# backplane.net
KiCad netlist of a schematic drawn in EAGLE
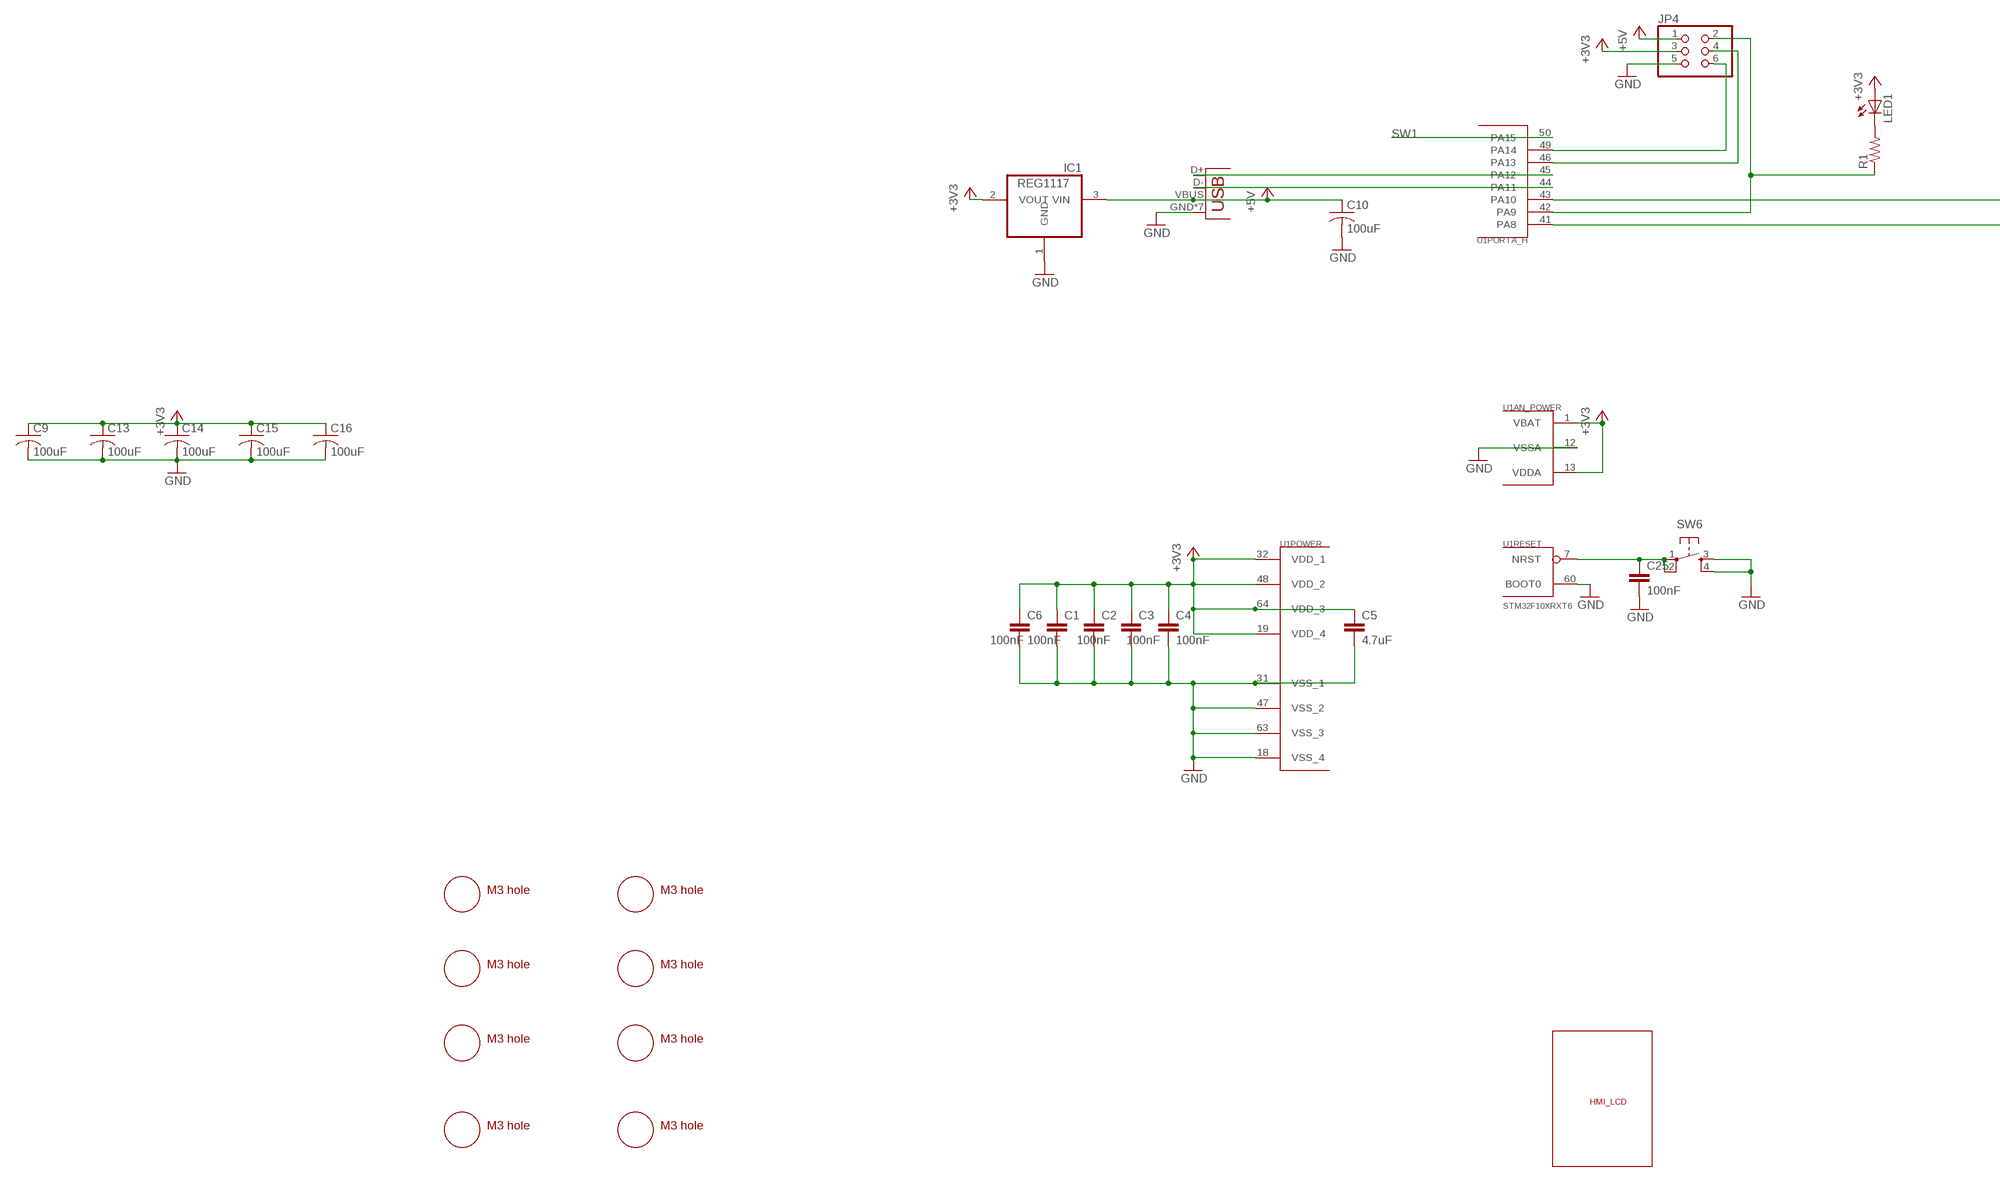
[diagram p0: schematic, sheet 1, part 1 of 2]
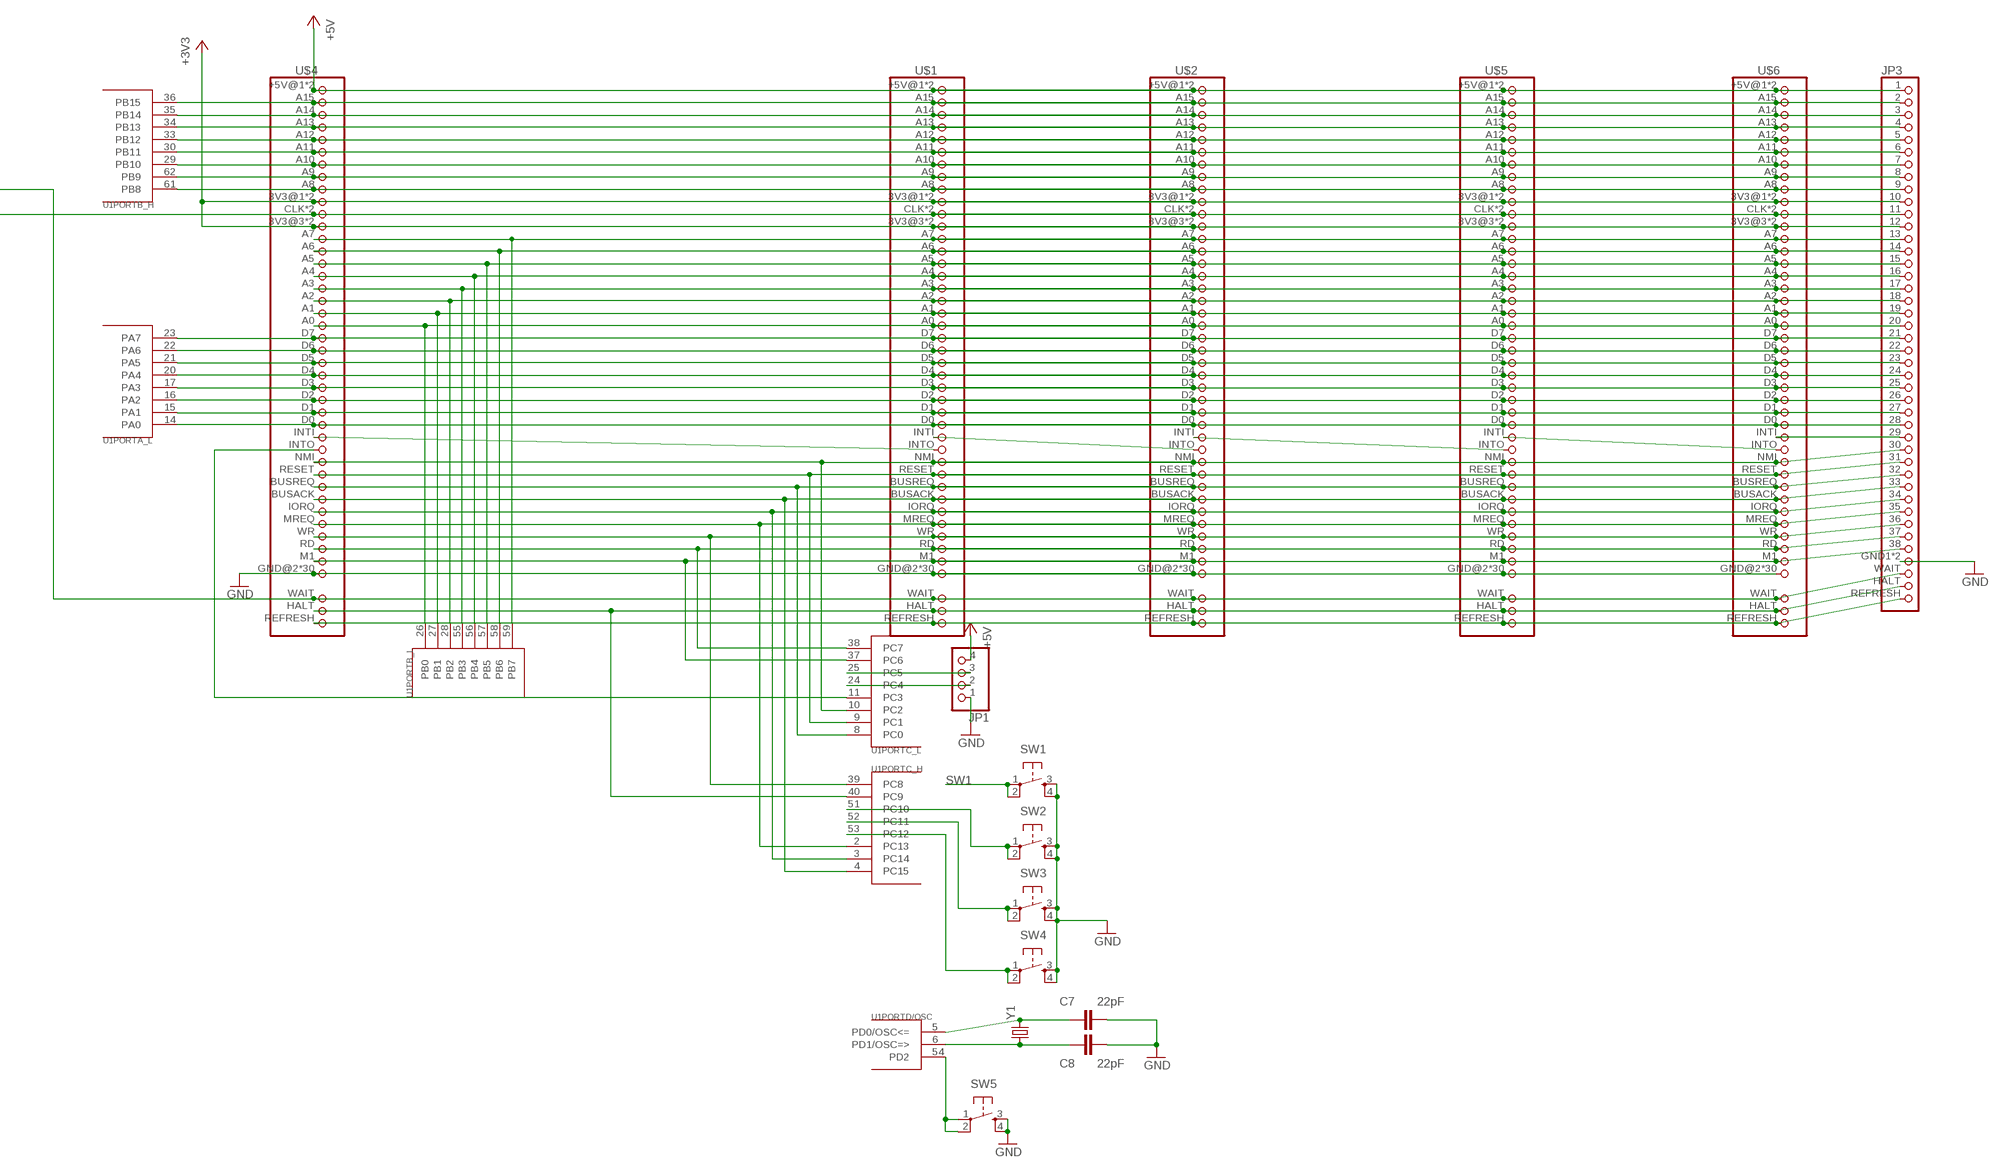
[diagram p1: schematic, sheet 1, part 2 of 2]

(export (version "E")
  (design (tool "Eeschema 10.0.6"))
  (components
    (comp (ref "C1")
      (value "100nF")
      (footprint "eagle-import:0805")
      (libsource (lib "eagle-import") (part "CAP0805"))
    )
    (comp (ref "C2")
      (value "100nF")
      (footprint "eagle-import:0805")
      (libsource (lib "eagle-import") (part "CAP0805"))
    )
    (comp (ref "C3")
      (value "100nF")
      (footprint "eagle-import:0805")
      (libsource (lib "eagle-import") (part "CAP0805"))
    )
    (comp (ref "C4")
      (value "100nF")
      (footprint "eagle-import:0805")
      (libsource (lib "eagle-import") (part "CAP0805"))
    )
    (comp (ref "C5")
      (value "4.7uF")
      (footprint "eagle-import:0805")
      (libsource (lib "eagle-import") (part "CAP0805"))
    )
    (comp (ref "C6")
      (value "100nF")
      (footprint "eagle-import:0805")
      (libsource (lib "eagle-import") (part "CAP0805"))
    )
    (comp (ref "C7")
      (value "22pF")
      (footprint "eagle-import:0805")
      (libsource (lib "eagle-import") (part "CAP0805"))
    )
    (comp (ref "C8")
      (value "22pF")
      (footprint "eagle-import:0805")
      (libsource (lib "eagle-import") (part "CAP0805"))
    )
    (comp (ref "C9")
      (value "100uF")
      (footprint "eagle-import:C1210")
      (libsource (lib "eagle-import") (part "C-USC1210"))
    )
    (comp (ref "C10")
      (value "100uF")
      (footprint "eagle-import:C1210")
      (libsource (lib "eagle-import") (part "C-USC1210"))
    )
    (comp (ref "C13")
      (value "100uF")
      (footprint "eagle-import:C1210")
      (libsource (lib "eagle-import") (part "C-USC1210"))
    )
    (comp (ref "C14")
      (value "100uF")
      (footprint "eagle-import:C1210")
      (libsource (lib "eagle-import") (part "C-USC1210"))
    )
    (comp (ref "C15")
      (value "100uF")
      (footprint "eagle-import:C1210")
      (libsource (lib "eagle-import") (part "C-USC1210"))
    )
    (comp (ref "C16")
      (value "100uF")
      (footprint "eagle-import:C1210")
      (libsource (lib "eagle-import") (part "C-USC1210"))
    )
    (comp (ref "C25")
      (value "100nF")
      (footprint "eagle-import:0805")
      (libsource (lib "eagle-import") (part "CAP0805"))
    )
    (comp (ref "IC1")
      (value "REG1117")
      (footprint "eagle-import:SOT223")
      (libsource (lib "eagle-import") (part "REG1117"))
    )
    (comp (ref "J1")
      (value "USB-MICROB")
      (footprint "eagle-import:USB-MICROB")
      (libsource (lib "eagle-import") (part "USB-MICROB"))
    )
    (comp (ref "JP1")
      (value "PINHD-1X4")
      (footprint "eagle-import:1X04")
      (libsource (lib "eagle-import") (part "PINHD-1X4"))
    )
    (comp (ref "JP3")
      (value "PINHD-1X38")
      (footprint "eagle-import:1X38")
      (libsource (lib "eagle-import") (part "PINHD-1X38"))
    )
    (comp (ref "JP4")
      (value "PINHD-2X3")
      (footprint "eagle-import:2X03")
      (libsource (lib "eagle-import") (part "PINHD-2X3"))
    )
    (comp (ref "LED1")
      (value "LEDCHIP-LED0805")
      (footprint "eagle-import:CHIP-LED0805")
      (libsource (lib "eagle-import") (part "LEDCHIP-LED0805"))
    )
    (comp (ref "R1")
      (value "R-US_R0805")
      (footprint "eagle-import:R0805")
      (libsource (lib "eagle-import") (part "R-US_R0805"))
    )
    (comp (ref "SW1")
      (value "SWITCH_SPST_4_PINSQUARE")
      (footprint "eagle-import:TACTILE-SWITCH-SMD")
      (libsource (lib "eagle-import") (part "SWITCH_SPST_4_PINSQUARE"))
    )
    (comp (ref "SW2")
      (value "SWITCH_SPST_4_PINSQUARE")
      (footprint "eagle-import:TACTILE-SWITCH-SMD")
      (libsource (lib "eagle-import") (part "SWITCH_SPST_4_PINSQUARE"))
    )
    (comp (ref "SW3")
      (value "SWITCH_SPST_4_PINSQUARE")
      (footprint "eagle-import:TACTILE-SWITCH-SMD")
      (libsource (lib "eagle-import") (part "SWITCH_SPST_4_PINSQUARE"))
    )
    (comp (ref "SW4")
      (value "SWITCH_SPST_4_PINSQUARE")
      (footprint "eagle-import:TACTILE-SWITCH-SMD")
      (libsource (lib "eagle-import") (part "SWITCH_SPST_4_PINSQUARE"))
    )
    (comp (ref "SW5")
      (value "SWITCH_SPST_4_PINSQUARE")
      (footprint "eagle-import:TACTILE-SWITCH-SMD")
      (libsource (lib "eagle-import") (part "SWITCH_SPST_4_PINSQUARE"))
    )
    (comp (ref "SW6")
      (value "SWITCH_SPST_4_PINSQUARE")
      (footprint "eagle-import:TACTILE-SWITCH-SMD")
      (libsource (lib "eagle-import") (part "SWITCH_SPST_4_PINSQUARE"))
    )
    (comp (ref "U$1")
      (value "FAP_BUS")
      (footprint "eagle-import:2X38")
      (libsource (lib "eagle-import") (part "FAP_BUS"))
    )
    (comp (ref "U$2")
      (value "FAP_BUS")
      (footprint "eagle-import:2X38")
      (libsource (lib "eagle-import") (part "FAP_BUS"))
    )
    (comp (ref "U$3")
      (value "HMI_LCD")
      (footprint "eagle-import:HMI_LCD")
      (libsource (lib "eagle-import") (part "HMI_LCD"))
    )
    (comp (ref "U$4")
      (value "FAP_BUS")
      (footprint "eagle-import:2X38")
      (libsource (lib "eagle-import") (part "FAP_BUS"))
    )
    (comp (ref "U$5")
      (value "FAP_BUS")
      (footprint "eagle-import:2X38")
      (libsource (lib "eagle-import") (part "FAP_BUS"))
    )
    (comp (ref "U$6")
      (value "FAP_BUS")
      (footprint "eagle-import:2X38")
      (libsource (lib "eagle-import") (part "FAP_BUS"))
    )
    (comp (ref "U$7")
      (value "M3_MOUNTING_HOLE")
      (footprint "eagle-import:M3_MOUNTING_HOLE_PACK")
      (libsource (lib "eagle-import") (part "M3_MOUNTING_HOLE"))
    )
    (comp (ref "U$8")
      (value "M3_MOUNTING_HOLE")
      (footprint "eagle-import:M3_MOUNTING_HOLE_PACK")
      (libsource (lib "eagle-import") (part "M3_MOUNTING_HOLE"))
    )
    (comp (ref "U$9")
      (value "M3_MOUNTING_HOLE")
      (footprint "eagle-import:M3_MOUNTING_HOLE_PACK")
      (libsource (lib "eagle-import") (part "M3_MOUNTING_HOLE"))
    )
    (comp (ref "U$10")
      (value "M3_MOUNTING_HOLE")
      (footprint "eagle-import:M3_MOUNTING_HOLE_PACK")
      (libsource (lib "eagle-import") (part "M3_MOUNTING_HOLE"))
    )
    (comp (ref "U$11")
      (value "M3_MOUNTING_HOLE")
      (footprint "eagle-import:M3_MOUNTING_HOLE_PACK")
      (libsource (lib "eagle-import") (part "M3_MOUNTING_HOLE"))
    )
    (comp (ref "U$12")
      (value "M3_MOUNTING_HOLE")
      (footprint "eagle-import:M3_MOUNTING_HOLE_PACK")
      (libsource (lib "eagle-import") (part "M3_MOUNTING_HOLE"))
    )
    (comp (ref "U$13")
      (value "M3_MOUNTING_HOLE")
      (footprint "eagle-import:M3_MOUNTING_HOLE_PACK")
      (libsource (lib "eagle-import") (part "M3_MOUNTING_HOLE"))
    )
    (comp (ref "U$14")
      (value "M3_MOUNTING_HOLE")
      (footprint "eagle-import:M3_MOUNTING_HOLE_PACK")
      (libsource (lib "eagle-import") (part "M3_MOUNTING_HOLE"))
    )
    (comp (ref "U1")
      (value "STM32F10XRXT6")
      (footprint "eagle-import:TQFP64")
      (libsource (lib "eagle-import") (part "STM32F10XRXT6"))
    )
    (comp (ref "Y1")
      (value "CRYSTALHC49US")
      (footprint "eagle-import:HC49US")
      (libsource (lib "eagle-import") (part "CRYSTALHC49US"))
    )
  )
  (nets
    (net (code "1") (name "+3V3") (class "Default")
      (node (ref "C1") (pin "1") (pinfunction "1_1") (pintype "passive"))
      (node (ref "C13") (pin "1") (pinfunction "1_1") (pintype "passive"))
      (node (ref "C14") (pin "1") (pinfunction "1_1") (pintype "passive"))
      (node (ref "C15") (pin "1") (pinfunction "1_1") (pintype "passive"))
      (node (ref "C16") (pin "1") (pinfunction "1_1") (pintype "passive"))
      (node (ref "C2") (pin "1") (pinfunction "1_1") (pintype "passive"))
      (node (ref "C3") (pin "1") (pinfunction "1_1") (pintype "passive"))
      (node (ref "C4") (pin "1") (pinfunction "1_1") (pintype "passive"))
      (node (ref "C5") (pin "1") (pinfunction "1_1") (pintype "passive"))
      (node (ref "C6") (pin "1") (pinfunction "1_1") (pintype "passive"))
      (node (ref "C9") (pin "1") (pinfunction "1_1") (pintype "passive"))
      (node (ref "IC1") (pin "2") (pinfunction "VOUT_2") (pintype "output"))
      (node (ref "JP3") (pin "10") (pinfunction "10_10") (pintype "passive"))
      (node (ref "JP3") (pin "12") (pinfunction "12_12") (pintype "passive"))
      (node (ref "JP4") (pin "3") (pinfunction "3_3") (pintype "passive"))
      (node (ref "LED1") (pin "A") (pinfunction "A_A") (pintype "passive"))
      (node (ref "U$1") (pin "3V3@1") (pinfunction "10_3V3@1") (pintype "passive"))
      (node (ref "U$1") (pin "3V3@2") (pinfunction "10_3V3@2") (pintype "passive"))
      (node (ref "U$1") (pin "3V3@3") (pinfunction "12_3V3@3") (pintype "passive"))
      (node (ref "U$1") (pin "3V3@4") (pinfunction "12_3V3@4") (pintype "passive"))
      (node (ref "U$2") (pin "3V3@1") (pinfunction "10_3V3@1") (pintype "passive"))
      (node (ref "U$2") (pin "3V3@2") (pinfunction "10_3V3@2") (pintype "passive"))
      (node (ref "U$2") (pin "3V3@3") (pinfunction "12_3V3@3") (pintype "passive"))
      (node (ref "U$2") (pin "3V3@4") (pinfunction "12_3V3@4") (pintype "passive"))
      (node (ref "U$4") (pin "3V3@1") (pinfunction "10_3V3@1") (pintype "passive"))
      (node (ref "U$4") (pin "3V3@2") (pinfunction "10_3V3@2") (pintype "passive"))
      (node (ref "U$4") (pin "3V3@3") (pinfunction "12_3V3@3") (pintype "passive"))
      (node (ref "U$4") (pin "3V3@4") (pinfunction "12_3V3@4") (pintype "passive"))
      (node (ref "U$5") (pin "3V3@1") (pinfunction "10_3V3@1") (pintype "passive"))
      (node (ref "U$5") (pin "3V3@2") (pinfunction "10_3V3@2") (pintype "passive"))
      (node (ref "U$5") (pin "3V3@3") (pinfunction "12_3V3@3") (pintype "passive"))
      (node (ref "U$5") (pin "3V3@4") (pinfunction "12_3V3@4") (pintype "passive"))
      (node (ref "U$6") (pin "3V3@1") (pinfunction "10_3V3@1") (pintype "passive"))
      (node (ref "U$6") (pin "3V3@2") (pinfunction "10_3V3@2") (pintype "passive"))
      (node (ref "U$6") (pin "3V3@3") (pinfunction "12_3V3@3") (pintype "passive"))
      (node (ref "U$6") (pin "3V3@4") (pinfunction "12_3V3@4") (pintype "passive"))
      (node (ref "U1") (pin "1") (pinfunction "VBAT_1") (pintype "power_in"))
      (node (ref "U1") (pin "13") (pinfunction "VDDA_13") (pintype "power_in"))
      (node (ref "U1") (pin "19") (pinfunction "VDD_4_19") (pintype "power_in"))
      (node (ref "U1") (pin "32") (pinfunction "VDD_1_32") (pintype "power_in"))
      (node (ref "U1") (pin "48") (pinfunction "VDD_2_48") (pintype "power_in"))
      (node (ref "U1") (pin "64") (pinfunction "VDD_3_64") (pintype "power_in"))
    )
    (net (code "2") (name "+5V") (class "Default")
      (node (ref "C10") (pin "1") (pinfunction "1_1") (pintype "passive"))
      (node (ref "IC1") (pin "3") (pinfunction "VIN_3") (pintype "input"))
      (node (ref "J1") (pin "VBUS") (pinfunction "VBUS_VBUS") (pintype "bidirectional"))
      (node (ref "JP1") (pin "4") (pinfunction "4_4") (pintype "passive"))
      (node (ref "JP3") (pin "1") (pinfunction "1_1") (pintype "passive"))
      (node (ref "JP4") (pin "1") (pinfunction "1_1") (pintype "passive"))
      (node (ref "U$1") (pin "+5V@1") (pinfunction "1_+5V@1") (pintype "passive"))
      (node (ref "U$1") (pin "+5V@2") (pinfunction "1_+5V@2") (pintype "passive"))
      (node (ref "U$2") (pin "+5V@1") (pinfunction "1_+5V@1") (pintype "passive"))
      (node (ref "U$2") (pin "+5V@2") (pinfunction "1_+5V@2") (pintype "passive"))
      (node (ref "U$4") (pin "+5V@1") (pinfunction "1_+5V@1") (pintype "passive"))
      (node (ref "U$4") (pin "+5V@2") (pinfunction "1_+5V@2") (pintype "passive"))
      (node (ref "U$5") (pin "+5V@1") (pinfunction "1_+5V@1") (pintype "passive"))
      (node (ref "U$5") (pin "+5V@2") (pinfunction "1_+5V@2") (pintype "passive"))
      (node (ref "U$6") (pin "+5V@1") (pinfunction "1_+5V@1") (pintype "passive"))
      (node (ref "U$6") (pin "+5V@2") (pinfunction "1_+5V@2") (pintype "passive"))
    )
    (net (code "3") (name "/SW1") (class "Default")
      (node (ref "SW1") (pin "1") (pinfunction "1_1") (pintype "passive"))
      (node (ref "SW1") (pin "2") (pinfunction "2_2") (pintype "passive"))
      (node (ref "U1") (pin "50") (pinfunction "PA15_50") (pintype "bidirectional"))
    )
    (net (code "4") (name "GND") (class "Default")
      (node (ref "C1") (pin "2") (pinfunction "2_2") (pintype "passive"))
      (node (ref "C10") (pin "2") (pinfunction "2_2") (pintype "passive"))
      (node (ref "C13") (pin "2") (pinfunction "2_2") (pintype "passive"))
      (node (ref "C14") (pin "2") (pinfunction "2_2") (pintype "passive"))
      (node (ref "C15") (pin "2") (pinfunction "2_2") (pintype "passive"))
      (node (ref "C16") (pin "2") (pinfunction "2_2") (pintype "passive"))
      (node (ref "C2") (pin "2") (pinfunction "2_2") (pintype "passive"))
      (node (ref "C25") (pin "2") (pinfunction "2_2") (pintype "passive"))
      (node (ref "C3") (pin "2") (pinfunction "2_2") (pintype "passive"))
      (node (ref "C4") (pin "2") (pinfunction "2_2") (pintype "passive"))
      (node (ref "C5") (pin "2") (pinfunction "2_2") (pintype "passive"))
      (node (ref "C6") (pin "2") (pinfunction "2_2") (pintype "passive"))
      (node (ref "C7") (pin "2") (pinfunction "2_2") (pintype "passive"))
      (node (ref "C8") (pin "2") (pinfunction "2_2") (pintype "passive"))
      (node (ref "C9") (pin "2") (pinfunction "2_2") (pintype "passive"))
      (node (ref "IC1") (pin "1") (pinfunction "GND_1") (pintype "power_in"))
      (node (ref "J1") (pin "GND") (pinfunction "GND_GND") (pintype "bidirectional"))
      (node (ref "J1") (pin "P1") (pinfunction "GND_P1") (pintype "bidirectional"))
      (node (ref "J1") (pin "P2") (pinfunction "GND_P2") (pintype "bidirectional"))
      (node (ref "J1") (pin "P3") (pinfunction "GND_P3") (pintype "bidirectional"))
      (node (ref "J1") (pin "P4") (pinfunction "GND_P4") (pintype "bidirectional"))
      (node (ref "J1") (pin "P5") (pinfunction "GND_P5") (pintype "bidirectional"))
      (node (ref "J1") (pin "P6") (pinfunction "GND_P6") (pintype "bidirectional"))
      (node (ref "JP1") (pin "1") (pinfunction "1_1") (pintype "passive"))
      (node (ref "JP3") (pin "GND1") (pinfunction "GND_GND1") (pintype "passive"))
      (node (ref "JP3") (pin "GND2") (pinfunction "GND_GND2") (pintype "passive"))
      (node (ref "JP4") (pin "5") (pinfunction "5_5") (pintype "passive"))
      (node (ref "SW1") (pin "3") (pinfunction "3_3") (pintype "passive"))
      (node (ref "SW1") (pin "4") (pinfunction "4_4") (pintype "passive"))
      (node (ref "SW2") (pin "3") (pinfunction "3_3") (pintype "passive"))
      (node (ref "SW2") (pin "4") (pinfunction "4_4") (pintype "passive"))
      (node (ref "SW3") (pin "3") (pinfunction "3_3") (pintype "passive"))
      (node (ref "SW3") (pin "4") (pinfunction "4_4") (pintype "passive"))
      (node (ref "SW4") (pin "3") (pinfunction "3_3") (pintype "passive"))
      (node (ref "SW4") (pin "4") (pinfunction "4_4") (pintype "passive"))
      (node (ref "SW5") (pin "3") (pinfunction "3_3") (pintype "passive"))
      (node (ref "SW5") (pin "4") (pinfunction "4_4") (pintype "passive"))
      (node (ref "SW6") (pin "3") (pinfunction "3_3") (pintype "passive"))
      (node (ref "SW6") (pin "4") (pinfunction "4_4") (pintype "passive"))
      (node (ref "U$1") (pin "GND@13") (pinfunction "GND_GND@13") (pintype "passive"))
      (node (ref "U$1") (pin "GND@14") (pinfunction "GND_GND@14") (pintype "passive"))
      (node (ref "U$1") (pin "GND@15") (pinfunction "GND_GND@15") (pintype "passive"))
      (node (ref "U$1") (pin "GND@16") (pinfunction "GND_GND@16") (pintype "passive"))
      (node (ref "U$1") (pin "GND@17") (pinfunction "GND_GND@17") (pintype "passive"))
      (node (ref "U$1") (pin "GND@18") (pinfunction "GND_GND@18") (pintype "passive"))
      (node (ref "U$1") (pin "GND@19") (pinfunction "GND_GND@19") (pintype "passive"))
      (node (ref "U$1") (pin "GND@2") (pinfunction "GND_GND@2") (pintype "passive"))
      (node (ref "U$1") (pin "GND@20") (pinfunction "GND_GND@20") (pintype "passive"))
      (node (ref "U$1") (pin "GND@21") (pinfunction "GND_GND@21") (pintype "passive"))
      (node (ref "U$1") (pin "GND@22") (pinfunction "GND_GND@22") (pintype "passive"))
      (node (ref "U$1") (pin "GND@23") (pinfunction "GND_GND@23") (pintype "passive"))
      (node (ref "U$1") (pin "GND@24") (pinfunction "GND_GND@24") (pintype "passive"))
      (node (ref "U$1") (pin "GND@25") (pinfunction "GND_GND@25") (pintype "passive"))
      (node (ref "U$1") (pin "GND@26") (pinfunction "GND_GND@26") (pintype "passive"))
      (node (ref "U$1") (pin "GND@27") (pinfunction "GND_GND@27") (pintype "passive"))
      (node (ref "U$1") (pin "GND@28") (pinfunction "GND_GND@28") (pintype "passive"))
      (node (ref "U$1") (pin "GND@3") (pinfunction "GND_GND@3") (pintype "passive"))
      (node (ref "U$1") (pin "GND@30") (pinfunction "GND_GND@30") (pintype "passive"))
      (node (ref "U$1") (pin "GND@34") (pinfunction "GND_GND@34") (pintype "passive"))
      (node (ref "U$1") (pin "GND@35") (pinfunction "GND_GND@35") (pintype "passive"))
      (node (ref "U$1") (pin "GND@36") (pinfunction "GND_GND@36") (pintype "passive"))
      (node (ref "U$1") (pin "GND@37") (pinfunction "GND_GND@37") (pintype "passive"))
      (node (ref "U$1") (pin "GND@38") (pinfunction "GND_GND@38") (pintype "passive"))
      (node (ref "U$1") (pin "GND@4") (pinfunction "GND_GND@4") (pintype "passive"))
      (node (ref "U$1") (pin "GND@5") (pinfunction "GND_GND@5") (pintype "passive"))
      (node (ref "U$1") (pin "GND@6") (pinfunction "GND_GND@6") (pintype "passive"))
      (node (ref "U$1") (pin "GND@7") (pinfunction "GND_GND@7") (pintype "passive"))
      (node (ref "U$1") (pin "GND@8") (pinfunction "GND_GND@8") (pintype "passive"))
      (node (ref "U$1") (pin "GND@9") (pinfunction "GND_GND@9") (pintype "passive"))
      (node (ref "U$2") (pin "GND@13") (pinfunction "GND_GND@13") (pintype "passive"))
      (node (ref "U$2") (pin "GND@14") (pinfunction "GND_GND@14") (pintype "passive"))
      (node (ref "U$2") (pin "GND@15") (pinfunction "GND_GND@15") (pintype "passive"))
      (node (ref "U$2") (pin "GND@16") (pinfunction "GND_GND@16") (pintype "passive"))
      (node (ref "U$2") (pin "GND@17") (pinfunction "GND_GND@17") (pintype "passive"))
      (node (ref "U$2") (pin "GND@18") (pinfunction "GND_GND@18") (pintype "passive"))
      (node (ref "U$2") (pin "GND@19") (pinfunction "GND_GND@19") (pintype "passive"))
      (node (ref "U$2") (pin "GND@2") (pinfunction "GND_GND@2") (pintype "passive"))
      (node (ref "U$2") (pin "GND@20") (pinfunction "GND_GND@20") (pintype "passive"))
      (node (ref "U$2") (pin "GND@21") (pinfunction "GND_GND@21") (pintype "passive"))
      (node (ref "U$2") (pin "GND@22") (pinfunction "GND_GND@22") (pintype "passive"))
      (node (ref "U$2") (pin "GND@23") (pinfunction "GND_GND@23") (pintype "passive"))
      (node (ref "U$2") (pin "GND@24") (pinfunction "GND_GND@24") (pintype "passive"))
      (node (ref "U$2") (pin "GND@25") (pinfunction "GND_GND@25") (pintype "passive"))
      (node (ref "U$2") (pin "GND@26") (pinfunction "GND_GND@26") (pintype "passive"))
      (node (ref "U$2") (pin "GND@27") (pinfunction "GND_GND@27") (pintype "passive"))
      (node (ref "U$2") (pin "GND@28") (pinfunction "GND_GND@28") (pintype "passive"))
      (node (ref "U$2") (pin "GND@3") (pinfunction "GND_GND@3") (pintype "passive"))
      (node (ref "U$2") (pin "GND@30") (pinfunction "GND_GND@30") (pintype "passive"))
      (node (ref "U$2") (pin "GND@34") (pinfunction "GND_GND@34") (pintype "passive"))
      (node (ref "U$2") (pin "GND@35") (pinfunction "GND_GND@35") (pintype "passive"))
      (node (ref "U$2") (pin "GND@36") (pinfunction "GND_GND@36") (pintype "passive"))
      (node (ref "U$2") (pin "GND@37") (pinfunction "GND_GND@37") (pintype "passive"))
      (node (ref "U$2") (pin "GND@38") (pinfunction "GND_GND@38") (pintype "passive"))
      (node (ref "U$2") (pin "GND@4") (pinfunction "GND_GND@4") (pintype "passive"))
      (node (ref "U$2") (pin "GND@5") (pinfunction "GND_GND@5") (pintype "passive"))
      (node (ref "U$2") (pin "GND@6") (pinfunction "GND_GND@6") (pintype "passive"))
      (node (ref "U$2") (pin "GND@7") (pinfunction "GND_GND@7") (pintype "passive"))
      (node (ref "U$2") (pin "GND@8") (pinfunction "GND_GND@8") (pintype "passive"))
      (node (ref "U$2") (pin "GND@9") (pinfunction "GND_GND@9") (pintype "passive"))
      (node (ref "U$4") (pin "GND@13") (pinfunction "GND_GND@13") (pintype "passive"))
      (node (ref "U$4") (pin "GND@14") (pinfunction "GND_GND@14") (pintype "passive"))
      (node (ref "U$4") (pin "GND@15") (pinfunction "GND_GND@15") (pintype "passive"))
      (node (ref "U$4") (pin "GND@16") (pinfunction "GND_GND@16") (pintype "passive"))
      (node (ref "U$4") (pin "GND@17") (pinfunction "GND_GND@17") (pintype "passive"))
      (node (ref "U$4") (pin "GND@18") (pinfunction "GND_GND@18") (pintype "passive"))
      (node (ref "U$4") (pin "GND@19") (pinfunction "GND_GND@19") (pintype "passive"))
      (node (ref "U$4") (pin "GND@2") (pinfunction "GND_GND@2") (pintype "passive"))
      (node (ref "U$4") (pin "GND@20") (pinfunction "GND_GND@20") (pintype "passive"))
      (node (ref "U$4") (pin "GND@21") (pinfunction "GND_GND@21") (pintype "passive"))
      (node (ref "U$4") (pin "GND@22") (pinfunction "GND_GND@22") (pintype "passive"))
      (node (ref "U$4") (pin "GND@23") (pinfunction "GND_GND@23") (pintype "passive"))
      (node (ref "U$4") (pin "GND@24") (pinfunction "GND_GND@24") (pintype "passive"))
      (node (ref "U$4") (pin "GND@25") (pinfunction "GND_GND@25") (pintype "passive"))
      (node (ref "U$4") (pin "GND@26") (pinfunction "GND_GND@26") (pintype "passive"))
      (node (ref "U$4") (pin "GND@27") (pinfunction "GND_GND@27") (pintype "passive"))
      (node (ref "U$4") (pin "GND@28") (pinfunction "GND_GND@28") (pintype "passive"))
      (node (ref "U$4") (pin "GND@3") (pinfunction "GND_GND@3") (pintype "passive"))
      (node (ref "U$4") (pin "GND@30") (pinfunction "GND_GND@30") (pintype "passive"))
      (node (ref "U$4") (pin "GND@34") (pinfunction "GND_GND@34") (pintype "passive"))
      (node (ref "U$4") (pin "GND@35") (pinfunction "GND_GND@35") (pintype "passive"))
      (node (ref "U$4") (pin "GND@36") (pinfunction "GND_GND@36") (pintype "passive"))
      (node (ref "U$4") (pin "GND@37") (pinfunction "GND_GND@37") (pintype "passive"))
      (node (ref "U$4") (pin "GND@38") (pinfunction "GND_GND@38") (pintype "passive"))
      (node (ref "U$4") (pin "GND@4") (pinfunction "GND_GND@4") (pintype "passive"))
      (node (ref "U$4") (pin "GND@5") (pinfunction "GND_GND@5") (pintype "passive"))
      (node (ref "U$4") (pin "GND@6") (pinfunction "GND_GND@6") (pintype "passive"))
      (node (ref "U$4") (pin "GND@7") (pinfunction "GND_GND@7") (pintype "passive"))
      (node (ref "U$4") (pin "GND@8") (pinfunction "GND_GND@8") (pintype "passive"))
      (node (ref "U$4") (pin "GND@9") (pinfunction "GND_GND@9") (pintype "passive"))
      (node (ref "U$5") (pin "GND@13") (pinfunction "GND_GND@13") (pintype "passive"))
      (node (ref "U$5") (pin "GND@14") (pinfunction "GND_GND@14") (pintype "passive"))
      (node (ref "U$5") (pin "GND@15") (pinfunction "GND_GND@15") (pintype "passive"))
      (node (ref "U$5") (pin "GND@16") (pinfunction "GND_GND@16") (pintype "passive"))
      (node (ref "U$5") (pin "GND@17") (pinfunction "GND_GND@17") (pintype "passive"))
      (node (ref "U$5") (pin "GND@18") (pinfunction "GND_GND@18") (pintype "passive"))
      (node (ref "U$5") (pin "GND@19") (pinfunction "GND_GND@19") (pintype "passive"))
      (node (ref "U$5") (pin "GND@2") (pinfunction "GND_GND@2") (pintype "passive"))
      (node (ref "U$5") (pin "GND@20") (pinfunction "GND_GND@20") (pintype "passive"))
      (node (ref "U$5") (pin "GND@21") (pinfunction "GND_GND@21") (pintype "passive"))
      (node (ref "U$5") (pin "GND@22") (pinfunction "GND_GND@22") (pintype "passive"))
      (node (ref "U$5") (pin "GND@23") (pinfunction "GND_GND@23") (pintype "passive"))
      (node (ref "U$5") (pin "GND@24") (pinfunction "GND_GND@24") (pintype "passive"))
      (node (ref "U$5") (pin "GND@25") (pinfunction "GND_GND@25") (pintype "passive"))
      (node (ref "U$5") (pin "GND@26") (pinfunction "GND_GND@26") (pintype "passive"))
      (node (ref "U$5") (pin "GND@27") (pinfunction "GND_GND@27") (pintype "passive"))
      (node (ref "U$5") (pin "GND@28") (pinfunction "GND_GND@28") (pintype "passive"))
      (node (ref "U$5") (pin "GND@3") (pinfunction "GND_GND@3") (pintype "passive"))
      (node (ref "U$5") (pin "GND@30") (pinfunction "GND_GND@30") (pintype "passive"))
      (node (ref "U$5") (pin "GND@34") (pinfunction "GND_GND@34") (pintype "passive"))
      (node (ref "U$5") (pin "GND@35") (pinfunction "GND_GND@35") (pintype "passive"))
      (node (ref "U$5") (pin "GND@36") (pinfunction "GND_GND@36") (pintype "passive"))
      (node (ref "U$5") (pin "GND@37") (pinfunction "GND_GND@37") (pintype "passive"))
      (node (ref "U$5") (pin "GND@38") (pinfunction "GND_GND@38") (pintype "passive"))
      (node (ref "U$5") (pin "GND@4") (pinfunction "GND_GND@4") (pintype "passive"))
      (node (ref "U$5") (pin "GND@5") (pinfunction "GND_GND@5") (pintype "passive"))
      (node (ref "U$5") (pin "GND@6") (pinfunction "GND_GND@6") (pintype "passive"))
      (node (ref "U$5") (pin "GND@7") (pinfunction "GND_GND@7") (pintype "passive"))
      (node (ref "U$5") (pin "GND@8") (pinfunction "GND_GND@8") (pintype "passive"))
      (node (ref "U$5") (pin "GND@9") (pinfunction "GND_GND@9") (pintype "passive"))
      (node (ref "U$6") (pin "GND@13") (pinfunction "GND_GND@13") (pintype "passive"))
      (node (ref "U$6") (pin "GND@14") (pinfunction "GND_GND@14") (pintype "passive"))
      (node (ref "U$6") (pin "GND@15") (pinfunction "GND_GND@15") (pintype "passive"))
      (node (ref "U$6") (pin "GND@16") (pinfunction "GND_GND@16") (pintype "passive"))
      (node (ref "U$6") (pin "GND@17") (pinfunction "GND_GND@17") (pintype "passive"))
      (node (ref "U$6") (pin "GND@18") (pinfunction "GND_GND@18") (pintype "passive"))
      (node (ref "U$6") (pin "GND@19") (pinfunction "GND_GND@19") (pintype "passive"))
      (node (ref "U$6") (pin "GND@2") (pinfunction "GND_GND@2") (pintype "passive"))
      (node (ref "U$6") (pin "GND@20") (pinfunction "GND_GND@20") (pintype "passive"))
      (node (ref "U$6") (pin "GND@21") (pinfunction "GND_GND@21") (pintype "passive"))
      (node (ref "U$6") (pin "GND@22") (pinfunction "GND_GND@22") (pintype "passive"))
      (node (ref "U$6") (pin "GND@23") (pinfunction "GND_GND@23") (pintype "passive"))
      (node (ref "U$6") (pin "GND@24") (pinfunction "GND_GND@24") (pintype "passive"))
      (node (ref "U$6") (pin "GND@25") (pinfunction "GND_GND@25") (pintype "passive"))
      (node (ref "U$6") (pin "GND@26") (pinfunction "GND_GND@26") (pintype "passive"))
      (node (ref "U$6") (pin "GND@27") (pinfunction "GND_GND@27") (pintype "passive"))
      (node (ref "U$6") (pin "GND@28") (pinfunction "GND_GND@28") (pintype "passive"))
      (node (ref "U$6") (pin "GND@3") (pinfunction "GND_GND@3") (pintype "passive"))
      (node (ref "U$6") (pin "GND@30") (pinfunction "GND_GND@30") (pintype "passive"))
      (node (ref "U$6") (pin "GND@34") (pinfunction "GND_GND@34") (pintype "passive"))
      (node (ref "U$6") (pin "GND@35") (pinfunction "GND_GND@35") (pintype "passive"))
      (node (ref "U$6") (pin "GND@36") (pinfunction "GND_GND@36") (pintype "passive"))
      (node (ref "U$6") (pin "GND@37") (pinfunction "GND_GND@37") (pintype "passive"))
      (node (ref "U$6") (pin "GND@38") (pinfunction "GND_GND@38") (pintype "passive"))
      (node (ref "U$6") (pin "GND@4") (pinfunction "GND_GND@4") (pintype "passive"))
      (node (ref "U$6") (pin "GND@5") (pinfunction "GND_GND@5") (pintype "passive"))
      (node (ref "U$6") (pin "GND@6") (pinfunction "GND_GND@6") (pintype "passive"))
      (node (ref "U$6") (pin "GND@7") (pinfunction "GND_GND@7") (pintype "passive"))
      (node (ref "U$6") (pin "GND@8") (pinfunction "GND_GND@8") (pintype "passive"))
      (node (ref "U$6") (pin "GND@9") (pinfunction "GND_GND@9") (pintype "passive"))
      (node (ref "U1") (pin "12") (pinfunction "VSSA_12") (pintype "power_in"))
      (node (ref "U1") (pin "18") (pinfunction "VSS_4_18") (pintype "power_in"))
      (node (ref "U1") (pin "31") (pinfunction "VSS_1_31") (pintype "power_in"))
      (node (ref "U1") (pin "47") (pinfunction "VSS_2_47") (pintype "power_in"))
      (node (ref "U1") (pin "60") (pinfunction "BOOT0_60") (pintype "input"))
      (node (ref "U1") (pin "63") (pinfunction "VSS_3_63") (pintype "power_in"))
    )
    (net (code "5") (name "Net-(JP3-PadREFRESH)") (class "Default")
      (node (ref "JP3") (pin "REFRESH") (pinfunction "REFRESH_REFRESH") (pintype "passive"))
      (node (ref "U$1") (pin "REFRESH") (pinfunction "REFRESH_REFRESH") (pintype "passive"))
      (node (ref "U$2") (pin "REFRESH") (pinfunction "REFRESH_REFRESH") (pintype "passive"))
      (node (ref "U$4") (pin "REFRESH") (pinfunction "REFRESH_REFRESH") (pintype "passive"))
      (node (ref "U$5") (pin "REFRESH") (pinfunction "REFRESH_REFRESH") (pintype "passive"))
      (node (ref "U$6") (pin "REFRESH") (pinfunction "REFRESH_REFRESH") (pintype "passive"))
    )
    (net (code "6") (name "Net-(LED1-PadC)") (class "Default")
      (node (ref "LED1") (pin "C") (pinfunction "C_C") (pintype "passive"))
      (node (ref "R1") (pin "2") (pinfunction "2_2") (pintype "passive"))
    )
    (net (code "7") (name "Net-(U$1-2)") (class "Default")
      (node (ref "JP3") (pin "2") (pinfunction "2_2") (pintype "passive"))
      (node (ref "U$1") (pin "A15") (pinfunction "2_A15") (pintype "passive"))
      (node (ref "U$2") (pin "A15") (pinfunction "2_A15") (pintype "passive"))
      (node (ref "U$4") (pin "A15") (pinfunction "2_A15") (pintype "passive"))
      (node (ref "U$5") (pin "A15") (pinfunction "2_A15") (pintype "passive"))
      (node (ref "U$6") (pin "A15") (pinfunction "2_A15") (pintype "passive"))
      (node (ref "U1") (pin "36") (pinfunction "PB15_36") (pintype "bidirectional"))
    )
    (net (code "8") (name "Net-(U$1-3)") (class "Default")
      (node (ref "JP3") (pin "3") (pinfunction "3_3") (pintype "passive"))
      (node (ref "U$1") (pin "A14") (pinfunction "3_A14") (pintype "passive"))
      (node (ref "U$2") (pin "A14") (pinfunction "3_A14") (pintype "passive"))
      (node (ref "U$4") (pin "A14") (pinfunction "3_A14") (pintype "passive"))
      (node (ref "U$5") (pin "A14") (pinfunction "3_A14") (pintype "passive"))
      (node (ref "U$6") (pin "A14") (pinfunction "3_A14") (pintype "passive"))
      (node (ref "U1") (pin "35") (pinfunction "PB14_35") (pintype "bidirectional"))
    )
    (net (code "9") (name "Net-(U$1-4)") (class "Default")
      (node (ref "JP3") (pin "4") (pinfunction "4_4") (pintype "passive"))
      (node (ref "U$1") (pin "A13") (pinfunction "4_A13") (pintype "passive"))
      (node (ref "U$2") (pin "A13") (pinfunction "4_A13") (pintype "passive"))
      (node (ref "U$4") (pin "A13") (pinfunction "4_A13") (pintype "passive"))
      (node (ref "U$5") (pin "A13") (pinfunction "4_A13") (pintype "passive"))
      (node (ref "U$6") (pin "A13") (pinfunction "4_A13") (pintype "passive"))
      (node (ref "U1") (pin "34") (pinfunction "PB13_34") (pintype "bidirectional"))
    )
    (net (code "10") (name "Net-(U$1-5)") (class "Default")
      (node (ref "JP3") (pin "5") (pinfunction "5_5") (pintype "passive"))
      (node (ref "U$1") (pin "A12") (pinfunction "5_A12") (pintype "passive"))
      (node (ref "U$2") (pin "A12") (pinfunction "5_A12") (pintype "passive"))
      (node (ref "U$4") (pin "A12") (pinfunction "5_A12") (pintype "passive"))
      (node (ref "U$5") (pin "A12") (pinfunction "5_A12") (pintype "passive"))
      (node (ref "U$6") (pin "A12") (pinfunction "5_A12") (pintype "passive"))
      (node (ref "U1") (pin "33") (pinfunction "PB12_33") (pintype "bidirectional"))
    )
    (net (code "11") (name "Net-(U$1-6)") (class "Default")
      (node (ref "JP3") (pin "6") (pinfunction "6_6") (pintype "passive"))
      (node (ref "U$1") (pin "A11") (pinfunction "6_A11") (pintype "passive"))
      (node (ref "U$2") (pin "A11") (pinfunction "6_A11") (pintype "passive"))
      (node (ref "U$4") (pin "A11") (pinfunction "6_A11") (pintype "passive"))
      (node (ref "U$5") (pin "A11") (pinfunction "6_A11") (pintype "passive"))
      (node (ref "U$6") (pin "A11") (pinfunction "6_A11") (pintype "passive"))
      (node (ref "U1") (pin "30") (pinfunction "PB11_30") (pintype "bidirectional"))
    )
    (net (code "12") (name "Net-(U$1-7)") (class "Default")
      (node (ref "JP3") (pin "7") (pinfunction "7_7") (pintype "passive"))
      (node (ref "U$1") (pin "A10") (pinfunction "7_A10") (pintype "passive"))
      (node (ref "U$2") (pin "A10") (pinfunction "7_A10") (pintype "passive"))
      (node (ref "U$4") (pin "A10") (pinfunction "7_A10") (pintype "passive"))
      (node (ref "U$5") (pin "A10") (pinfunction "7_A10") (pintype "passive"))
      (node (ref "U$6") (pin "A10") (pinfunction "7_A10") (pintype "passive"))
      (node (ref "U1") (pin "29") (pinfunction "PB10_29") (pintype "bidirectional"))
    )
    (net (code "13") (name "Net-(U$1-8)") (class "Default")
      (node (ref "JP3") (pin "8") (pinfunction "8_8") (pintype "passive"))
      (node (ref "U$1") (pin "A9") (pinfunction "8_A9") (pintype "passive"))
      (node (ref "U$2") (pin "A9") (pinfunction "8_A9") (pintype "passive"))
      (node (ref "U$4") (pin "A9") (pinfunction "8_A9") (pintype "passive"))
      (node (ref "U$5") (pin "A9") (pinfunction "8_A9") (pintype "passive"))
      (node (ref "U$6") (pin "A9") (pinfunction "8_A9") (pintype "passive"))
      (node (ref "U1") (pin "62") (pinfunction "PB9_62") (pintype "bidirectional"))
    )
    (net (code "14") (name "Net-(U$1-9)") (class "Default")
      (node (ref "JP3") (pin "9") (pinfunction "9_9") (pintype "passive"))
      (node (ref "U$1") (pin "A8") (pinfunction "9_A8") (pintype "passive"))
      (node (ref "U$2") (pin "A8") (pinfunction "9_A8") (pintype "passive"))
      (node (ref "U$4") (pin "A8") (pinfunction "9_A8") (pintype "passive"))
      (node (ref "U$5") (pin "A8") (pinfunction "9_A8") (pintype "passive"))
      (node (ref "U$6") (pin "A8") (pinfunction "9_A8") (pintype "passive"))
      (node (ref "U1") (pin "61") (pinfunction "PB8_61") (pintype "bidirectional"))
    )
    (net (code "15") (name "Net-(U$1-13)") (class "Default")
      (node (ref "JP3") (pin "13") (pinfunction "13_13") (pintype "passive"))
      (node (ref "U$1") (pin "A7") (pinfunction "13_A7") (pintype "passive"))
      (node (ref "U$2") (pin "A7") (pinfunction "13_A7") (pintype "passive"))
      (node (ref "U$4") (pin "A7") (pinfunction "13_A7") (pintype "passive"))
      (node (ref "U$5") (pin "A7") (pinfunction "13_A7") (pintype "passive"))
      (node (ref "U$6") (pin "A7") (pinfunction "13_A7") (pintype "passive"))
      (node (ref "U1") (pin "59") (pinfunction "PB7_59") (pintype "bidirectional"))
    )
    (net (code "16") (name "Net-(U$1-14)") (class "Default")
      (node (ref "JP3") (pin "14") (pinfunction "14_14") (pintype "passive"))
      (node (ref "U$1") (pin "A6") (pinfunction "14_A6") (pintype "passive"))
      (node (ref "U$2") (pin "A6") (pinfunction "14_A6") (pintype "passive"))
      (node (ref "U$4") (pin "A6") (pinfunction "14_A6") (pintype "passive"))
      (node (ref "U$5") (pin "A6") (pinfunction "14_A6") (pintype "passive"))
      (node (ref "U$6") (pin "A6") (pinfunction "14_A6") (pintype "passive"))
      (node (ref "U1") (pin "58") (pinfunction "PB6_58") (pintype "bidirectional"))
    )
    (net (code "17") (name "Net-(U$1-15)") (class "Default")
      (node (ref "JP3") (pin "15") (pinfunction "15_15") (pintype "passive"))
      (node (ref "U$1") (pin "A5") (pinfunction "15_A5") (pintype "passive"))
      (node (ref "U$2") (pin "A5") (pinfunction "15_A5") (pintype "passive"))
      (node (ref "U$4") (pin "A5") (pinfunction "15_A5") (pintype "passive"))
      (node (ref "U$5") (pin "A5") (pinfunction "15_A5") (pintype "passive"))
      (node (ref "U$6") (pin "A5") (pinfunction "15_A5") (pintype "passive"))
      (node (ref "U1") (pin "57") (pinfunction "PB5_57") (pintype "bidirectional"))
    )
    (net (code "18") (name "Net-(U$1-16)") (class "Default")
      (node (ref "JP3") (pin "16") (pinfunction "16_16") (pintype "passive"))
      (node (ref "U$1") (pin "A4") (pinfunction "16_A4") (pintype "passive"))
      (node (ref "U$2") (pin "A4") (pinfunction "16_A4") (pintype "passive"))
      (node (ref "U$4") (pin "A4") (pinfunction "16_A4") (pintype "passive"))
      (node (ref "U$5") (pin "A4") (pinfunction "16_A4") (pintype "passive"))
      (node (ref "U$6") (pin "A4") (pinfunction "16_A4") (pintype "passive"))
      (node (ref "U1") (pin "56") (pinfunction "PB4_56") (pintype "bidirectional"))
    )
    (net (code "19") (name "Net-(U$1-17)") (class "Default")
      (node (ref "JP3") (pin "17") (pinfunction "17_17") (pintype "passive"))
      (node (ref "U$1") (pin "A3") (pinfunction "17_A3") (pintype "passive"))
      (node (ref "U$2") (pin "A3") (pinfunction "17_A3") (pintype "passive"))
      (node (ref "U$4") (pin "A3") (pinfunction "17_A3") (pintype "passive"))
      (node (ref "U$5") (pin "A3") (pinfunction "17_A3") (pintype "passive"))
      (node (ref "U$6") (pin "A3") (pinfunction "17_A3") (pintype "passive"))
      (node (ref "U1") (pin "55") (pinfunction "PB3_55") (pintype "bidirectional"))
    )
    (net (code "20") (name "Net-(U$1-18)") (class "Default")
      (node (ref "JP3") (pin "18") (pinfunction "18_18") (pintype "passive"))
      (node (ref "U$1") (pin "A2") (pinfunction "18_A2") (pintype "passive"))
      (node (ref "U$2") (pin "A2") (pinfunction "18_A2") (pintype "passive"))
      (node (ref "U$4") (pin "A2") (pinfunction "18_A2") (pintype "passive"))
      (node (ref "U$5") (pin "A2") (pinfunction "18_A2") (pintype "passive"))
      (node (ref "U$6") (pin "A2") (pinfunction "18_A2") (pintype "passive"))
      (node (ref "U1") (pin "28") (pinfunction "PB2_28") (pintype "bidirectional"))
    )
    (net (code "21") (name "Net-(U$1-19)") (class "Default")
      (node (ref "JP3") (pin "19") (pinfunction "19_19") (pintype "passive"))
      (node (ref "U$1") (pin "A1") (pinfunction "19_A1") (pintype "passive"))
      (node (ref "U$2") (pin "A1") (pinfunction "19_A1") (pintype "passive"))
      (node (ref "U$4") (pin "A1") (pinfunction "19_A1") (pintype "passive"))
      (node (ref "U$5") (pin "A1") (pinfunction "19_A1") (pintype "passive"))
      (node (ref "U$6") (pin "A1") (pinfunction "19_A1") (pintype "passive"))
      (node (ref "U1") (pin "27") (pinfunction "PB1_27") (pintype "bidirectional"))
    )
    (net (code "22") (name "Net-(U$1-20)") (class "Default")
      (node (ref "JP3") (pin "20") (pinfunction "20_20") (pintype "passive"))
      (node (ref "U$1") (pin "A0") (pinfunction "20_A0") (pintype "passive"))
      (node (ref "U$2") (pin "A0") (pinfunction "20_A0") (pintype "passive"))
      (node (ref "U$4") (pin "A0") (pinfunction "20_A0") (pintype "passive"))
      (node (ref "U$5") (pin "A0") (pinfunction "20_A0") (pintype "passive"))
      (node (ref "U$6") (pin "A0") (pinfunction "20_A0") (pintype "passive"))
      (node (ref "U1") (pin "26") (pinfunction "PB0_26") (pintype "bidirectional"))
    )
    (net (code "23") (name "Net-(U$1-21)") (class "Default")
      (node (ref "JP3") (pin "21") (pinfunction "21_21") (pintype "passive"))
      (node (ref "U$1") (pin "D7") (pinfunction "21_D7") (pintype "passive"))
      (node (ref "U$2") (pin "D7") (pinfunction "21_D7") (pintype "passive"))
      (node (ref "U$4") (pin "D7") (pinfunction "21_D7") (pintype "passive"))
      (node (ref "U$5") (pin "D7") (pinfunction "21_D7") (pintype "passive"))
      (node (ref "U$6") (pin "D7") (pinfunction "21_D7") (pintype "passive"))
      (node (ref "U1") (pin "23") (pinfunction "PA7_23") (pintype "bidirectional"))
    )
    (net (code "24") (name "Net-(U$1-22)") (class "Default")
      (node (ref "JP3") (pin "22") (pinfunction "22_22") (pintype "passive"))
      (node (ref "U$1") (pin "D6") (pinfunction "22_D6") (pintype "passive"))
      (node (ref "U$2") (pin "D6") (pinfunction "22_D6") (pintype "passive"))
      (node (ref "U$4") (pin "D6") (pinfunction "22_D6") (pintype "passive"))
      (node (ref "U$5") (pin "D6") (pinfunction "22_D6") (pintype "passive"))
      (node (ref "U$6") (pin "D6") (pinfunction "22_D6") (pintype "passive"))
      (node (ref "U1") (pin "22") (pinfunction "PA6_22") (pintype "bidirectional"))
    )
    (net (code "25") (name "Net-(U$1-23)") (class "Default")
      (node (ref "JP3") (pin "23") (pinfunction "23_23") (pintype "passive"))
      (node (ref "U$1") (pin "D5") (pinfunction "23_D5") (pintype "passive"))
      (node (ref "U$2") (pin "D5") (pinfunction "23_D5") (pintype "passive"))
      (node (ref "U$4") (pin "D5") (pinfunction "23_D5") (pintype "passive"))
      (node (ref "U$5") (pin "D5") (pinfunction "23_D5") (pintype "passive"))
      (node (ref "U$6") (pin "D5") (pinfunction "23_D5") (pintype "passive"))
      (node (ref "U1") (pin "21") (pinfunction "PA5_21") (pintype "bidirectional"))
    )
    (net (code "26") (name "Net-(U$1-24)") (class "Default")
      (node (ref "JP3") (pin "24") (pinfunction "24_24") (pintype "passive"))
      (node (ref "U$1") (pin "D4") (pinfunction "24_D4") (pintype "passive"))
      (node (ref "U$2") (pin "D4") (pinfunction "24_D4") (pintype "passive"))
      (node (ref "U$4") (pin "D4") (pinfunction "24_D4") (pintype "passive"))
      (node (ref "U$5") (pin "D4") (pinfunction "24_D4") (pintype "passive"))
      (node (ref "U$6") (pin "D4") (pinfunction "24_D4") (pintype "passive"))
      (node (ref "U1") (pin "20") (pinfunction "PA4_20") (pintype "bidirectional"))
    )
    (net (code "27") (name "Net-(U$1-25)") (class "Default")
      (node (ref "JP3") (pin "25") (pinfunction "25_25") (pintype "passive"))
      (node (ref "U$1") (pin "D3") (pinfunction "25_D3") (pintype "passive"))
      (node (ref "U$2") (pin "D3") (pinfunction "25_D3") (pintype "passive"))
      (node (ref "U$4") (pin "D3") (pinfunction "25_D3") (pintype "passive"))
      (node (ref "U$5") (pin "D3") (pinfunction "25_D3") (pintype "passive"))
      (node (ref "U$6") (pin "D3") (pinfunction "25_D3") (pintype "passive"))
      (node (ref "U1") (pin "17") (pinfunction "PA3_17") (pintype "bidirectional"))
    )
    (net (code "28") (name "Net-(U$1-26)") (class "Default")
      (node (ref "JP3") (pin "26") (pinfunction "26_26") (pintype "passive"))
      (node (ref "U$1") (pin "D2") (pinfunction "26_D2") (pintype "passive"))
      (node (ref "U$2") (pin "D2") (pinfunction "26_D2") (pintype "passive"))
      (node (ref "U$4") (pin "D2") (pinfunction "26_D2") (pintype "passive"))
      (node (ref "U$5") (pin "D2") (pinfunction "26_D2") (pintype "passive"))
      (node (ref "U$6") (pin "D2") (pinfunction "26_D2") (pintype "passive"))
      (node (ref "U1") (pin "16") (pinfunction "PA2_16") (pintype "bidirectional"))
    )
    (net (code "29") (name "Net-(U$1-27)") (class "Default")
      (node (ref "JP3") (pin "27") (pinfunction "27_27") (pintype "passive"))
      (node (ref "U$1") (pin "D1") (pinfunction "27_D1") (pintype "passive"))
      (node (ref "U$2") (pin "D1") (pinfunction "27_D1") (pintype "passive"))
      (node (ref "U$4") (pin "D1") (pinfunction "27_D1") (pintype "passive"))
      (node (ref "U$5") (pin "D1") (pinfunction "27_D1") (pintype "passive"))
      (node (ref "U$6") (pin "D1") (pinfunction "27_D1") (pintype "passive"))
      (node (ref "U1") (pin "15") (pinfunction "PA1_15") (pintype "bidirectional"))
    )
    (net (code "30") (name "Net-(U$1-28)") (class "Default")
      (node (ref "JP3") (pin "28") (pinfunction "28_28") (pintype "passive"))
      (node (ref "U$1") (pin "D0") (pinfunction "28_D0") (pintype "passive"))
      (node (ref "U$2") (pin "D0") (pinfunction "28_D0") (pintype "passive"))
      (node (ref "U$4") (pin "D0") (pinfunction "28_D0") (pintype "passive"))
      (node (ref "U$5") (pin "D0") (pinfunction "28_D0") (pintype "passive"))
      (node (ref "U$6") (pin "D0") (pinfunction "28_D0") (pintype "passive"))
      (node (ref "U1") (pin "14") (pinfunction "PA0_14") (pintype "bidirectional"))
    )
    (net (code "31") (name "Net-(U$1-29)") (class "Default")
      (node (ref "U$1") (pin "INTI") (pinfunction "29_INTI") (pintype "passive"))
      (node (ref "U$2") (pin "INTO") (pinfunction "39_INTO") (pintype "passive"))
    )
    (net (code "32") (name "Net-(U$1-30)") (class "Default")
      (node (ref "JP3") (pin "30") (pinfunction "30_30") (pintype "passive"))
      (node (ref "U$1") (pin "NMI") (pinfunction "30_NMI") (pintype "passive"))
      (node (ref "U$2") (pin "NMI") (pinfunction "30_NMI") (pintype "passive"))
      (node (ref "U$4") (pin "NMI") (pinfunction "30_NMI") (pintype "passive"))
      (node (ref "U$5") (pin "NMI") (pinfunction "30_NMI") (pintype "passive"))
      (node (ref "U$6") (pin "NMI") (pinfunction "30_NMI") (pintype "passive"))
      (node (ref "U1") (pin "10") (pinfunction "PC2_10") (pintype "bidirectional"))
    )
    (net (code "33") (name "Net-(U$1-31)") (class "Default")
      (node (ref "JP3") (pin "31") (pinfunction "31_31") (pintype "passive"))
      (node (ref "U$1") (pin "RESET") (pinfunction "31_RESET") (pintype "passive"))
      (node (ref "U$2") (pin "RESET") (pinfunction "31_RESET") (pintype "passive"))
      (node (ref "U$4") (pin "RESET") (pinfunction "31_RESET") (pintype "passive"))
      (node (ref "U$5") (pin "RESET") (pinfunction "31_RESET") (pintype "passive"))
      (node (ref "U$6") (pin "RESET") (pinfunction "31_RESET") (pintype "passive"))
      (node (ref "U1") (pin "9") (pinfunction "PC1_9") (pintype "bidirectional"))
    )
    (net (code "34") (name "Net-(U$1-32)") (class "Default")
      (node (ref "JP3") (pin "32") (pinfunction "32_32") (pintype "passive"))
      (node (ref "U$1") (pin "BUSREQ") (pinfunction "32_BUSREQ") (pintype "passive"))
      (node (ref "U$2") (pin "BUSREQ") (pinfunction "32_BUSREQ") (pintype "passive"))
      (node (ref "U$4") (pin "BUSREQ") (pinfunction "32_BUSREQ") (pintype "passive"))
      (node (ref "U$5") (pin "BUSREQ") (pinfunction "32_BUSREQ") (pintype "passive"))
      (node (ref "U$6") (pin "BUSREQ") (pinfunction "32_BUSREQ") (pintype "passive"))
      (node (ref "U1") (pin "8") (pinfunction "PC0_8") (pintype "bidirectional"))
    )
    (net (code "35") (name "Net-(U$1-33)") (class "Default")
      (node (ref "JP3") (pin "33") (pinfunction "33_33") (pintype "passive"))
      (node (ref "U$1") (pin "BUSACK") (pinfunction "33_BUSACK") (pintype "passive"))
      (node (ref "U$2") (pin "BUSACK") (pinfunction "33_BUSACK") (pintype "passive"))
      (node (ref "U$4") (pin "BUSACK") (pinfunction "33_BUSACK") (pintype "passive"))
      (node (ref "U$5") (pin "BUSACK") (pinfunction "33_BUSACK") (pintype "passive"))
      (node (ref "U$6") (pin "BUSACK") (pinfunction "33_BUSACK") (pintype "passive"))
      (node (ref "U1") (pin "4") (pinfunction "PC15_4") (pintype "bidirectional"))
    )
    (net (code "36") (name "Net-(U$1-34)") (class "Default")
      (node (ref "JP3") (pin "34") (pinfunction "34_34") (pintype "passive"))
      (node (ref "U$1") (pin "IORQ") (pinfunction "34_IORQ") (pintype "passive"))
      (node (ref "U$2") (pin "IORQ") (pinfunction "34_IORQ") (pintype "passive"))
      (node (ref "U$4") (pin "IORQ") (pinfunction "34_IORQ") (pintype "passive"))
      (node (ref "U$5") (pin "IORQ") (pinfunction "34_IORQ") (pintype "passive"))
      (node (ref "U$6") (pin "IORQ") (pinfunction "34_IORQ") (pintype "passive"))
      (node (ref "U1") (pin "3") (pinfunction "PC14_3") (pintype "bidirectional"))
    )
    (net (code "37") (name "Net-(U$1-35)") (class "Default")
      (node (ref "JP3") (pin "35") (pinfunction "35_35") (pintype "passive"))
      (node (ref "U$1") (pin "MREQ") (pinfunction "35_MREQ") (pintype "passive"))
      (node (ref "U$2") (pin "MREQ") (pinfunction "35_MREQ") (pintype "passive"))
      (node (ref "U$4") (pin "MREQ") (pinfunction "35_MREQ") (pintype "passive"))
      (node (ref "U$5") (pin "MREQ") (pinfunction "35_MREQ") (pintype "passive"))
      (node (ref "U$6") (pin "MREQ") (pinfunction "35_MREQ") (pintype "passive"))
      (node (ref "U1") (pin "2") (pinfunction "PC13_2") (pintype "bidirectional"))
    )
    (net (code "38") (name "Net-(U$1-36)") (class "Default")
      (node (ref "JP3") (pin "36") (pinfunction "36_36") (pintype "passive"))
      (node (ref "U$1") (pin "WR") (pinfunction "36_WR") (pintype "passive"))
      (node (ref "U$2") (pin "WR") (pinfunction "36_WR") (pintype "passive"))
      (node (ref "U$4") (pin "WR") (pinfunction "36_WR") (pintype "passive"))
      (node (ref "U$5") (pin "WR") (pinfunction "36_WR") (pintype "passive"))
      (node (ref "U$6") (pin "WR") (pinfunction "36_WR") (pintype "passive"))
      (node (ref "U1") (pin "39") (pinfunction "PC8_39") (pintype "bidirectional"))
    )
    (net (code "39") (name "Net-(U$1-37)") (class "Default")
      (node (ref "JP3") (pin "37") (pinfunction "37_37") (pintype "passive"))
      (node (ref "U$1") (pin "RD") (pinfunction "37_RD") (pintype "passive"))
      (node (ref "U$2") (pin "RD") (pinfunction "37_RD") (pintype "passive"))
      (node (ref "U$4") (pin "RD") (pinfunction "37_RD") (pintype "passive"))
      (node (ref "U$5") (pin "RD") (pinfunction "37_RD") (pintype "passive"))
      (node (ref "U$6") (pin "RD") (pinfunction "37_RD") (pintype "passive"))
      (node (ref "U1") (pin "38") (pinfunction "PC7_38") (pintype "bidirectional"))
    )
    (net (code "40") (name "Net-(U$1-38)") (class "Default")
      (node (ref "JP3") (pin "38") (pinfunction "38_38") (pintype "passive"))
      (node (ref "U$1") (pin "M1") (pinfunction "38_M1") (pintype "passive"))
      (node (ref "U$2") (pin "M1") (pinfunction "38_M1") (pintype "passive"))
      (node (ref "U$4") (pin "M1") (pinfunction "38_M1") (pintype "passive"))
      (node (ref "U$5") (pin "M1") (pinfunction "38_M1") (pintype "passive"))
      (node (ref "U$6") (pin "M1") (pinfunction "38_M1") (pintype "passive"))
      (node (ref "U1") (pin "37") (pinfunction "PC6_37") (pintype "bidirectional"))
    )
    (net (code "41") (name "Net-(U$1-39)") (class "Default")
      (node (ref "U$1") (pin "INTO") (pinfunction "39_INTO") (pintype "passive"))
      (node (ref "U$4") (pin "INTI") (pinfunction "29_INTI") (pintype "passive"))
    )
    (net (code "42") (name "Net-(U$2-29)") (class "Default")
      (node (ref "U$2") (pin "INTI") (pinfunction "29_INTI") (pintype "passive"))
      (node (ref "U$5") (pin "INTO") (pinfunction "39_INTO") (pintype "passive"))
    )
    (net (code "43") (name "Net-(U$4-39)") (class "Default")
      (node (ref "U$4") (pin "INTO") (pinfunction "39_INTO") (pintype "passive"))
      (node (ref "U1") (pin "11") (pinfunction "PC3_11") (pintype "bidirectional"))
    )
    (net (code "44") (name "Net-(U$5-29)") (class "Default")
      (node (ref "U$5") (pin "INTI") (pinfunction "29_INTI") (pintype "passive"))
      (node (ref "U$6") (pin "INTO") (pinfunction "39_INTO") (pintype "passive"))
    )
    (net (code "45") (name "Net-(U$6-29)") (class "Default")
      (node (ref "JP3") (pin "29") (pinfunction "29_29") (pintype "passive"))
      (node (ref "U$6") (pin "INTI") (pinfunction "29_INTI") (pintype "passive"))
    )
    (net (code "46") (name "Net-(U1B-PA8)") (class "Default")
      (node (ref "JP3") (pin "11") (pinfunction "11_11") (pintype "passive"))
      (node (ref "U$1") (pin "CLK") (pinfunction "11_CLK") (pintype "passive"))
      (node (ref "U$1") (pin "CLK@2") (pinfunction "11_CLK@2") (pintype "passive"))
      (node (ref "U$2") (pin "CLK") (pinfunction "11_CLK") (pintype "passive"))
      (node (ref "U$2") (pin "CLK@2") (pinfunction "11_CLK@2") (pintype "passive"))
      (node (ref "U$4") (pin "CLK") (pinfunction "11_CLK") (pintype "passive"))
      (node (ref "U$4") (pin "CLK@2") (pinfunction "11_CLK@2") (pintype "passive"))
      (node (ref "U$5") (pin "CLK") (pinfunction "11_CLK") (pintype "passive"))
      (node (ref "U$5") (pin "CLK@2") (pinfunction "11_CLK@2") (pintype "passive"))
      (node (ref "U$6") (pin "CLK") (pinfunction "11_CLK") (pintype "passive"))
      (node (ref "U$6") (pin "CLK@2") (pinfunction "11_CLK@2") (pintype "passive"))
      (node (ref "U1") (pin "41") (pinfunction "PA8_41") (pintype "bidirectional"))
    )
    (net (code "47") (name "Net-(U1B-PA9)") (class "Default")
      (node (ref "JP4") (pin "2") (pinfunction "2_2") (pintype "passive"))
      (node (ref "R1") (pin "1") (pinfunction "1_1") (pintype "passive"))
      (node (ref "U1") (pin "42") (pinfunction "PA9_42") (pintype "bidirectional"))
    )
    (net (code "48") (name "Net-(U1B-PA10)") (class "Default")
      (node (ref "JP3") (pin "WAIT") (pinfunction "WAIT_WAIT") (pintype "passive"))
      (node (ref "U$1") (pin "WAIT") (pinfunction "WAIT_WAIT") (pintype "passive"))
      (node (ref "U$2") (pin "WAIT") (pinfunction "WAIT_WAIT") (pintype "passive"))
      (node (ref "U$4") (pin "WAIT") (pinfunction "WAIT_WAIT") (pintype "passive"))
      (node (ref "U$5") (pin "WAIT") (pinfunction "WAIT_WAIT") (pintype "passive"))
      (node (ref "U$6") (pin "WAIT") (pinfunction "WAIT_WAIT") (pintype "passive"))
      (node (ref "U1") (pin "43") (pinfunction "PA10_43") (pintype "bidirectional"))
    )
    (net (code "49") (name "Net-(U1B-PA11)") (class "Default")
      (node (ref "J1") (pin "D-") (pinfunction "D-_D-") (pintype "bidirectional"))
      (node (ref "U1") (pin "44") (pinfunction "PA11_44") (pintype "bidirectional"))
    )
    (net (code "50") (name "Net-(U1B-PA12)") (class "Default")
      (node (ref "J1") (pin "D+") (pinfunction "D+_D+") (pintype "bidirectional"))
      (node (ref "U1") (pin "45") (pinfunction "PA12_45") (pintype "bidirectional"))
    )
    (net (code "51") (name "Net-(U1B-PA13)") (class "Default")
      (node (ref "JP4") (pin "4") (pinfunction "4_4") (pintype "passive"))
      (node (ref "U1") (pin "46") (pinfunction "PA13_46") (pintype "bidirectional"))
    )
    (net (code "52") (name "Net-(U1B-PA14)") (class "Default")
      (node (ref "JP4") (pin "6") (pinfunction "6_6") (pintype "passive"))
      (node (ref "U1") (pin "49") (pinfunction "PA14_49") (pintype "bidirectional"))
    )
    (net (code "53") (name "Net-(U1F-PC9)") (class "Default")
      (node (ref "JP3") (pin "HALT") (pinfunction "HALT_HALT") (pintype "passive"))
      (node (ref "U$1") (pin "HALT") (pinfunction "HALT_HALT") (pintype "passive"))
      (node (ref "U$2") (pin "HALT") (pinfunction "HALT_HALT") (pintype "passive"))
      (node (ref "U$4") (pin "HALT") (pinfunction "HALT_HALT") (pintype "passive"))
      (node (ref "U$5") (pin "HALT") (pinfunction "HALT_HALT") (pintype "passive"))
      (node (ref "U$6") (pin "HALT") (pinfunction "HALT_HALT") (pintype "passive"))
      (node (ref "U1") (pin "40") (pinfunction "PC9_40") (pintype "bidirectional"))
    )
    (net (code "54") (name "Net-(U1F-PC10)") (class "Default")
      (node (ref "SW2") (pin "1") (pinfunction "1_1") (pintype "passive"))
      (node (ref "SW2") (pin "2") (pinfunction "2_2") (pintype "passive"))
      (node (ref "U1") (pin "51") (pinfunction "PC10_51") (pintype "bidirectional"))
    )
    (net (code "55") (name "Net-(U1F-PC11)") (class "Default")
      (node (ref "SW3") (pin "1") (pinfunction "1_1") (pintype "passive"))
      (node (ref "SW3") (pin "2") (pinfunction "2_2") (pintype "passive"))
      (node (ref "U1") (pin "52") (pinfunction "PC11_52") (pintype "bidirectional"))
    )
    (net (code "56") (name "Net-(U1F-PC12)") (class "Default")
      (node (ref "SW4") (pin "1") (pinfunction "1_1") (pintype "passive"))
      (node (ref "SW4") (pin "2") (pinfunction "2_2") (pintype "passive"))
      (node (ref "U1") (pin "53") (pinfunction "PC12_53") (pintype "bidirectional"))
    )
    (net (code "57") (name "Net-(U1G-PC4)") (class "Default")
      (node (ref "JP1") (pin "2") (pinfunction "2_2") (pintype "passive"))
      (node (ref "U1") (pin "24") (pinfunction "PC4_24") (pintype "bidirectional"))
    )
    (net (code "58") (name "Net-(U1G-PC5)") (class "Default")
      (node (ref "JP1") (pin "3") (pinfunction "3_3") (pintype "passive"))
      (node (ref "U1") (pin "25") (pinfunction "PC5_25") (pintype "bidirectional"))
    )
    (net (code "59") (name "Net-(U1H-PD0{slash}OSC<=)") (class "Default")
      (node (ref "C7") (pin "1") (pinfunction "1_1") (pintype "passive"))
      (node (ref "U1") (pin "5") (pinfunction "PD0/OSC<=_5") (pintype "bidirectional"))
      (node (ref "Y1") (pin "2") (pinfunction "2_2") (pintype "passive"))
    )
    (net (code "60") (name "Net-(U1H-PD1{slash}OSC=>)") (class "Default")
      (node (ref "C8") (pin "1") (pinfunction "1_1") (pintype "passive"))
      (node (ref "U1") (pin "6") (pinfunction "PD1/OSC=>_6") (pintype "bidirectional"))
      (node (ref "Y1") (pin "1") (pinfunction "1_1") (pintype "passive"))
    )
    (net (code "61") (name "Net-(U1H-PD2)") (class "Default")
      (node (ref "SW5") (pin "1") (pinfunction "1_1") (pintype "passive"))
      (node (ref "SW5") (pin "2") (pinfunction "2_2") (pintype "passive"))
      (node (ref "U1") (pin "54") (pinfunction "PD2_54") (pintype "bidirectional"))
    )
    (net (code "62") (name "Net-(U1J-NRST)") (class "Default")
      (node (ref "C25") (pin "1") (pinfunction "1_1") (pintype "passive"))
      (node (ref "SW6") (pin "1") (pinfunction "1_1") (pintype "passive"))
      (node (ref "SW6") (pin "2") (pinfunction "2_2") (pintype "passive"))
      (node (ref "U1") (pin "7") (pinfunction "NRST_7") (pintype "input"))
    )
  )
)
